# Sheet1.net
KiCad netlist of a schematic drawn in Altium Designer
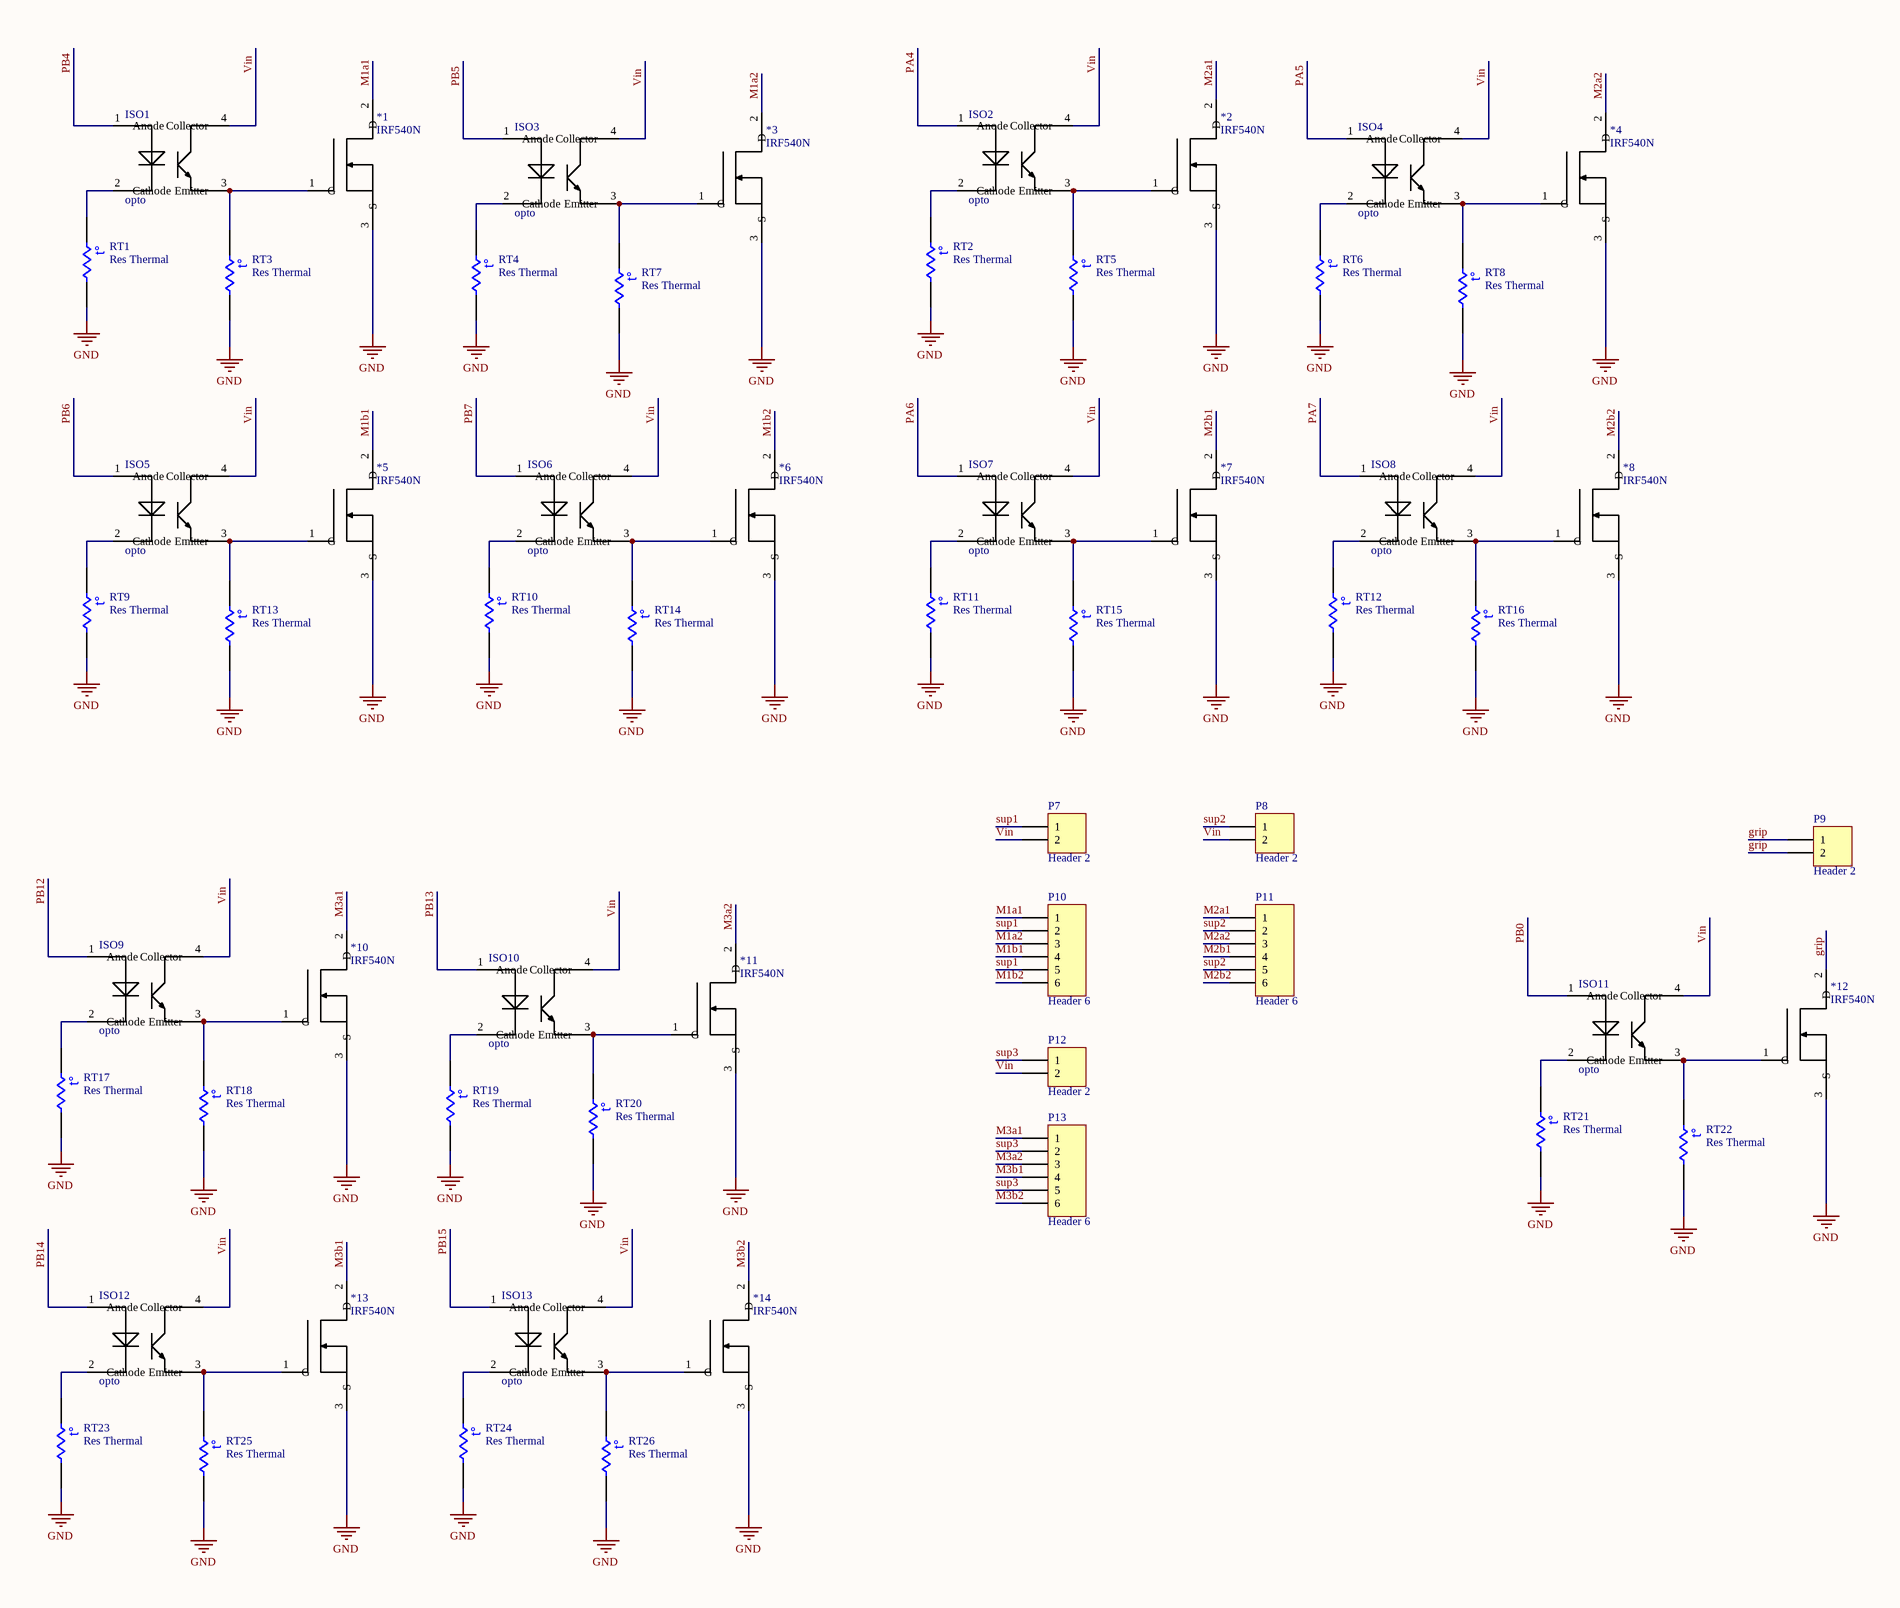
[diagram p0: Sheet1.SchDoc, left]
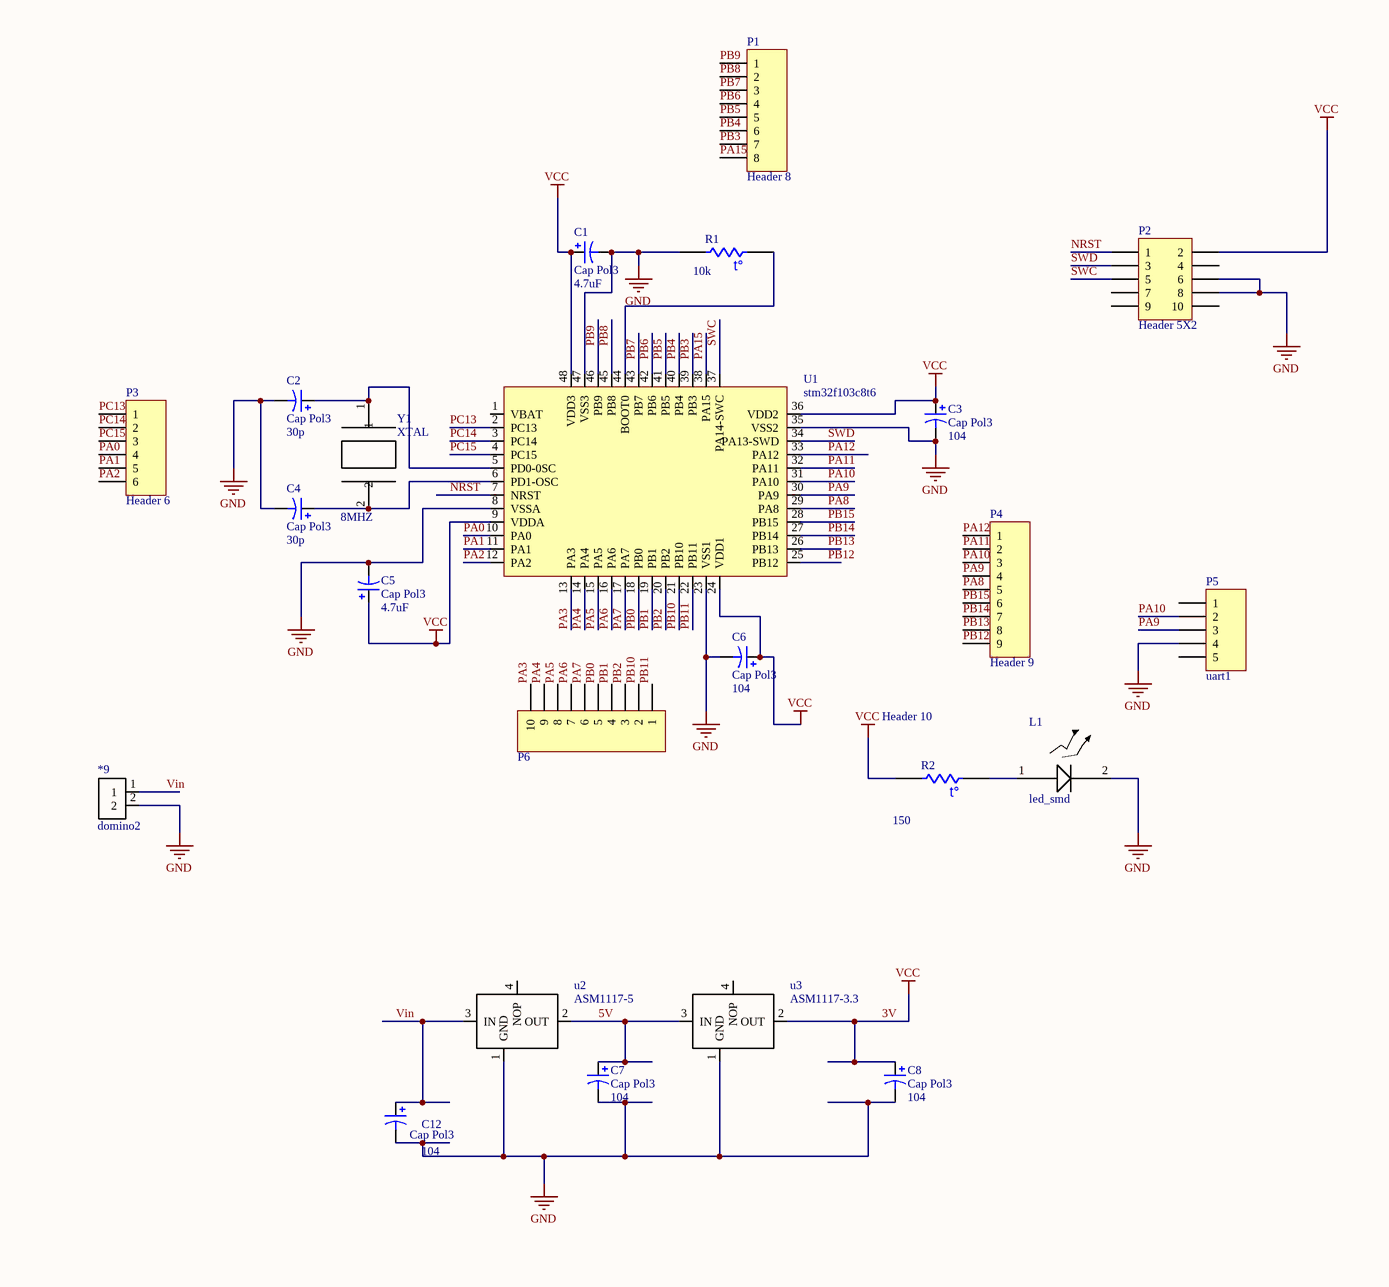
[diagram p1: Sheet1.SchDoc, right]

(export (version "E")
  (design (tool "Eeschema 10.0.6"))
  (components
    (comp (ref "*1")
      (value "IRF540N")
      (footprint "Pcbforslave:TO220")
      (libsource (lib "Schlib1") (part "IRF540N"))
    )
    (comp (ref "*2")
      (value "IRF540N")
      (footprint "Pcbforslave:TO220")
      (libsource (lib "Schlib1") (part "IRF540N"))
    )
    (comp (ref "*3")
      (value "IRF540N")
      (footprint "Pcbforslave:TO220")
      (libsource (lib "Schlib1") (part "IRF540N"))
    )
    (comp (ref "*4")
      (value "IRF540N")
      (footprint "Pcbforslave:TO220")
      (libsource (lib "Schlib1") (part "IRF540N"))
    )
    (comp (ref "*5")
      (value "IRF540N")
      (footprint "Pcbforslave:TO220")
      (libsource (lib "Schlib1") (part "IRF540N"))
    )
    (comp (ref "*6")
      (value "IRF540N")
      (footprint "Pcbforslave:TO220")
      (libsource (lib "Schlib1") (part "IRF540N"))
    )
    (comp (ref "*7")
      (value "IRF540N")
      (footprint "Pcbforslave:TO220")
      (libsource (lib "Schlib1") (part "IRF540N"))
    )
    (comp (ref "*8")
      (value "IRF540N")
      (footprint "Pcbforslave:TO220")
      (libsource (lib "Schlib1") (part "IRF540N"))
    )
    (comp (ref "*9")
      (value "domino2")
      (footprint "Pcbforslave:Domino_2")
      (libsource (lib "Schlib1") (part "domino2"))
    )
    (comp (ref "*10")
      (value "IRF540N")
      (footprint "Pcbforslave:TO220")
      (libsource (lib "Schlib1") (part "IRF540N"))
    )
    (comp (ref "*11")
      (value "IRF540N")
      (footprint "Pcbforslave:TO220")
      (libsource (lib "Schlib1") (part "IRF540N"))
    )
    (comp (ref "*12")
      (value "IRF540N")
      (footprint "Pcbforslave:TO220")
      (libsource (lib "Schlib1") (part "IRF540N"))
    )
    (comp (ref "*13")
      (value "IRF540N")
      (footprint "Pcbforslave:TO220")
      (libsource (lib "Schlib1") (part "IRF540N"))
    )
    (comp (ref "*14")
      (value "IRF540N")
      (footprint "Pcbforslave:TO220")
      (libsource (lib "Schlib1") (part "IRF540N"))
    )
    (comp (ref "C1")
      (value "Cap Pol3")
      (footprint "C0805")
      (description "Polarized Capacitor (Surface Mount)")
      (fields (field (name "ALTIUM_VALUE") "4.7uF") (field (name "PUBLISHER") "Altium Limited"))
      (libsource (lib "Miscellaneous Devices") (part "Cap Pol3"))
    )
    (comp (ref "C2")
      (value "Cap Pol3")
      (footprint "C0805")
      (description "Polarized Capacitor (Surface Mount)")
      (fields (field (name "ALTIUM_VALUE") "30p") (field (name "PUBLISHER") "Altium Limited"))
      (libsource (lib "Miscellaneous Devices") (part "Cap Pol3"))
    )
    (comp (ref "C3")
      (value "Cap Pol3")
      (footprint "C0805")
      (description "Polarized Capacitor (Surface Mount)")
      (fields (field (name "ALTIUM_VALUE") "104") (field (name "PUBLISHER") "Altium Limited"))
      (libsource (lib "Miscellaneous Devices") (part "Cap Pol3"))
    )
    (comp (ref "C4")
      (value "Cap Pol3")
      (footprint "C0805")
      (description "Polarized Capacitor (Surface Mount)")
      (fields (field (name "ALTIUM_VALUE") "30p") (field (name "PUBLISHER") "Altium Limited"))
      (libsource (lib "Miscellaneous Devices") (part "Cap Pol3"))
    )
    (comp (ref "C5")
      (value "Cap Pol3")
      (footprint "C0805")
      (description "Polarized Capacitor (Surface Mount)")
      (fields (field (name "ALTIUM_VALUE") "4.7uF") (field (name "PUBLISHER") "Altium Limited"))
      (libsource (lib "Miscellaneous Devices") (part "Cap Pol3"))
    )
    (comp (ref "C6")
      (value "Cap Pol3")
      (footprint "C0805")
      (description "Polarized Capacitor (Surface Mount)")
      (fields (field (name "ALTIUM_VALUE") "104") (field (name "PUBLISHER") "Altium Limited"))
      (libsource (lib "Miscellaneous Devices") (part "Cap Pol3"))
    )
    (comp (ref "C7")
      (value "Cap Pol3")
      (footprint "C0805")
      (description "Polarized Capacitor (Surface Mount)")
      (fields (field (name "ALTIUM_VALUE") "104") (field (name "PUBLISHER") "Altium Limited"))
      (libsource (lib "Miscellaneous Devices") (part "Cap Pol3"))
    )
    (comp (ref "C8")
      (value "Cap Pol3")
      (footprint "C0805")
      (description "Polarized Capacitor (Surface Mount)")
      (fields (field (name "ALTIUM_VALUE") "104") (field (name "PUBLISHER") "Altium Limited"))
      (libsource (lib "Miscellaneous Devices") (part "Cap Pol3"))
    )
    (comp (ref "C12")
      (value "Cap Pol3")
      (footprint "C0805")
      (description "Polarized Capacitor (Surface Mount)")
      (fields (field (name "ALTIUM_VALUE") "104") (field (name "PUBLISHER") "Altium Limited"))
      (libsource (lib "Miscellaneous Devices") (part "Cap Pol3"))
    )
    (comp (ref "ISO1")
      (value "opto")
      (footprint "Pcbforslave:opto_smd")
      (libsource (lib "Schlib1") (part "opto"))
    )
    (comp (ref "ISO2")
      (value "opto")
      (footprint "Pcbforslave:opto_smd")
      (libsource (lib "Schlib1") (part "opto"))
    )
    (comp (ref "ISO3")
      (value "opto")
      (footprint "Pcbforslave:opto_smd")
      (libsource (lib "Schlib1") (part "opto"))
    )
    (comp (ref "ISO4")
      (value "opto")
      (footprint "Pcbforslave:opto_smd")
      (libsource (lib "Schlib1") (part "opto"))
    )
    (comp (ref "ISO5")
      (value "opto")
      (footprint "Pcbforslave:opto_smd")
      (libsource (lib "Schlib1") (part "opto"))
    )
    (comp (ref "ISO6")
      (value "opto")
      (footprint "Pcbforslave:opto_smd")
      (libsource (lib "Schlib1") (part "opto"))
    )
    (comp (ref "ISO7")
      (value "opto")
      (footprint "Pcbforslave:opto_smd")
      (libsource (lib "Schlib1") (part "opto"))
    )
    (comp (ref "ISO8")
      (value "opto")
      (footprint "Pcbforslave:opto_smd")
      (libsource (lib "Schlib1") (part "opto"))
    )
    (comp (ref "ISO9")
      (value "opto")
      (footprint "Pcbforslave:opto_smd")
      (libsource (lib "Schlib1") (part "opto"))
    )
    (comp (ref "ISO10")
      (value "opto")
      (footprint "Pcbforslave:opto_smd")
      (libsource (lib "Schlib1") (part "opto"))
    )
    (comp (ref "ISO11")
      (value "opto")
      (footprint "Pcbforslave:opto_smd")
      (libsource (lib "Schlib1") (part "opto"))
    )
    (comp (ref "ISO12")
      (value "opto")
      (footprint "Pcbforslave:opto_smd")
      (libsource (lib "Schlib1") (part "opto"))
    )
    (comp (ref "ISO13")
      (value "opto")
      (footprint "Pcbforslave:opto_smd")
      (libsource (lib "Schlib1") (part "opto"))
    )
    (comp (ref "L1") (value "led_smd") (footprint "led_smd") (libsource (lib "Schlib1") (part "led_smd")))
    (comp (ref "P1")
      (value "Header 8")
      (footprint "HDR1X8")
      (description "Header, 8-Pin")
      (fields (field (name "PUBLISHER") "Altium Limited"))
      (libsource (lib "Miscellaneous Connectors") (part "Header 8"))
    )
    (comp (ref "P2")
      (value "Header 5X2")
      (footprint "HDR2X5")
      (description "Header, 5-Pin, Dual row")
      (fields (field (name "PUBLISHER") "Altium Limited"))
      (libsource (lib "Miscellaneous Connectors") (part "Header 5X2"))
    )
    (comp (ref "P3")
      (value "Header 6")
      (footprint "HDR1X6")
      (description "Header, 6-Pin")
      (fields (field (name "PUBLISHER") "Altium Limited"))
      (libsource (lib "Miscellaneous Connectors") (part "Header 6"))
    )
    (comp (ref "P4")
      (value "Header 9")
      (footprint "HDR1X9")
      (description "Header, 9-Pin")
      (fields (field (name "PUBLISHER") "Altium Limited"))
      (libsource (lib "Miscellaneous Connectors") (part "Header 9"))
    )
    (comp (ref "P5")
      (value "uart1")
      (footprint "HDR1X5")
      (description "Header, 5-Pin")
      (fields (field (name "PUBLISHER") "Altium Limited"))
      (libsource (lib "Miscellaneous Connectors") (part "Header 5"))
    )
    (comp (ref "P6")
      (value "Header 10")
      (footprint "HDR1X10")
      (description "Header, 10-Pin")
      (fields (field (name "PUBLISHER") "Altium Limited"))
      (libsource (lib "Miscellaneous Connectors") (part "Header 10"))
    )
    (comp (ref "P7")
      (value "Header 2")
      (footprint "HDR1X2")
      (description "Header, 2-Pin")
      (fields (field (name "PUBLISHER") "Altium Limited"))
      (libsource (lib "Miscellaneous Connectors") (part "Header 2"))
    )
    (comp (ref "P8")
      (value "Header 2")
      (footprint "HDR1X2")
      (description "Header, 2-Pin")
      (fields (field (name "PUBLISHER") "Altium Limited"))
      (libsource (lib "Miscellaneous Connectors") (part "Header 2"))
    )
    (comp (ref "P9")
      (value "Header 2")
      (footprint "HDR1X2")
      (description "Header, 2-Pin")
      (fields (field (name "PUBLISHER") "Altium Limited"))
      (libsource (lib "Miscellaneous Connectors") (part "Header 2"))
    )
    (comp (ref "P10")
      (value "Header 6")
      (footprint "HDR1X6")
      (description "Header, 6-Pin")
      (fields (field (name "PUBLISHER") "Altium Limited"))
      (libsource (lib "Miscellaneous Connectors") (part "Header 6"))
    )
    (comp (ref "P11")
      (value "Header 6")
      (footprint "HDR1X6")
      (description "Header, 6-Pin")
      (fields (field (name "PUBLISHER") "Altium Limited"))
      (libsource (lib "Miscellaneous Connectors") (part "Header 6"))
    )
    (comp (ref "P12")
      (value "Header 2")
      (footprint "HDR1X2")
      (description "Header, 2-Pin")
      (fields (field (name "PUBLISHER") "Altium Limited"))
      (libsource (lib "Miscellaneous Connectors") (part "Header 2"))
    )
    (comp (ref "P13")
      (value "Header 6")
      (footprint "HDR1X6")
      (description "Header, 6-Pin")
      (fields (field (name "PUBLISHER") "Altium Limited"))
      (libsource (lib "Miscellaneous Connectors") (part "Header 6"))
    )
    (comp (ref "R1")
      (value "10k")
      (footprint "6-0805_N")
      (description "Thermistor")
      (fields (field (name "PUBLISHER") "Altium Limited"))
      (libsource (lib "Miscellaneous Devices") (part "Res Thermal"))
    )
    (comp (ref "R2")
      (value "150")
      (footprint "6-0805_N")
      (description "Thermistor")
      (fields (field (name "PUBLISHER") "Altium Limited"))
      (libsource (lib "Miscellaneous Devices") (part "Res Thermal"))
    )
    (comp (ref "RT1")
      (value "Res Thermal")
      (footprint "6-0805_N")
      (description "Thermistor")
      (fields (field (name "PUBLISHER") "Altium Limited"))
      (libsource (lib "Miscellaneous Devices") (part "Res Thermal"))
    )
    (comp (ref "RT2")
      (value "Res Thermal")
      (footprint "6-0805_N")
      (description "Thermistor")
      (fields (field (name "PUBLISHER") "Altium Limited"))
      (libsource (lib "Miscellaneous Devices") (part "Res Thermal"))
    )
    (comp (ref "RT3")
      (value "Res Thermal")
      (footprint "6-0805_N")
      (description "Thermistor")
      (fields (field (name "PUBLISHER") "Altium Limited"))
      (libsource (lib "Miscellaneous Devices") (part "Res Thermal"))
    )
    (comp (ref "RT4")
      (value "Res Thermal")
      (footprint "6-0805_N")
      (description "Thermistor")
      (fields (field (name "PUBLISHER") "Altium Limited"))
      (libsource (lib "Miscellaneous Devices") (part "Res Thermal"))
    )
    (comp (ref "RT5")
      (value "Res Thermal")
      (footprint "6-0805_N")
      (description "Thermistor")
      (fields (field (name "PUBLISHER") "Altium Limited"))
      (libsource (lib "Miscellaneous Devices") (part "Res Thermal"))
    )
    (comp (ref "RT6")
      (value "Res Thermal")
      (footprint "6-0805_N")
      (description "Thermistor")
      (fields (field (name "PUBLISHER") "Altium Limited"))
      (libsource (lib "Miscellaneous Devices") (part "Res Thermal"))
    )
    (comp (ref "RT7")
      (value "Res Thermal")
      (footprint "6-0805_N")
      (description "Thermistor")
      (fields (field (name "PUBLISHER") "Altium Limited"))
      (libsource (lib "Miscellaneous Devices") (part "Res Thermal"))
    )
    (comp (ref "RT8")
      (value "Res Thermal")
      (footprint "6-0805_N")
      (description "Thermistor")
      (fields (field (name "PUBLISHER") "Altium Limited"))
      (libsource (lib "Miscellaneous Devices") (part "Res Thermal"))
    )
    (comp (ref "RT9")
      (value "Res Thermal")
      (footprint "6-0805_N")
      (description "Thermistor")
      (fields (field (name "PUBLISHER") "Altium Limited"))
      (libsource (lib "Miscellaneous Devices") (part "Res Thermal"))
    )
    (comp (ref "RT10")
      (value "Res Thermal")
      (footprint "6-0805_N")
      (description "Thermistor")
      (fields (field (name "PUBLISHER") "Altium Limited"))
      (libsource (lib "Miscellaneous Devices") (part "Res Thermal"))
    )
    (comp (ref "RT11")
      (value "Res Thermal")
      (footprint "6-0805_N")
      (description "Thermistor")
      (fields (field (name "PUBLISHER") "Altium Limited"))
      (libsource (lib "Miscellaneous Devices") (part "Res Thermal"))
    )
    (comp (ref "RT12")
      (value "Res Thermal")
      (footprint "6-0805_N")
      (description "Thermistor")
      (fields (field (name "PUBLISHER") "Altium Limited"))
      (libsource (lib "Miscellaneous Devices") (part "Res Thermal"))
    )
    (comp (ref "RT13")
      (value "Res Thermal")
      (footprint "6-0805_N")
      (description "Thermistor")
      (fields (field (name "PUBLISHER") "Altium Limited"))
      (libsource (lib "Miscellaneous Devices") (part "Res Thermal"))
    )
    (comp (ref "RT14")
      (value "Res Thermal")
      (footprint "6-0805_N")
      (description "Thermistor")
      (fields (field (name "PUBLISHER") "Altium Limited"))
      (libsource (lib "Miscellaneous Devices") (part "Res Thermal"))
    )
    (comp (ref "RT15")
      (value "Res Thermal")
      (footprint "6-0805_N")
      (description "Thermistor")
      (fields (field (name "PUBLISHER") "Altium Limited"))
      (libsource (lib "Miscellaneous Devices") (part "Res Thermal"))
    )
    (comp (ref "RT16")
      (value "Res Thermal")
      (footprint "6-0805_N")
      (description "Thermistor")
      (fields (field (name "PUBLISHER") "Altium Limited"))
      (libsource (lib "Miscellaneous Devices") (part "Res Thermal"))
    )
    (comp (ref "RT17")
      (value "Res Thermal")
      (footprint "6-0805_N")
      (description "Thermistor")
      (fields (field (name "PUBLISHER") "Altium Limited"))
      (libsource (lib "Miscellaneous Devices") (part "Res Thermal"))
    )
    (comp (ref "RT18")
      (value "Res Thermal")
      (footprint "6-0805_N")
      (description "Thermistor")
      (fields (field (name "PUBLISHER") "Altium Limited"))
      (libsource (lib "Miscellaneous Devices") (part "Res Thermal"))
    )
    (comp (ref "RT19")
      (value "Res Thermal")
      (footprint "6-0805_N")
      (description "Thermistor")
      (fields (field (name "PUBLISHER") "Altium Limited"))
      (libsource (lib "Miscellaneous Devices") (part "Res Thermal"))
    )
    (comp (ref "RT20")
      (value "Res Thermal")
      (footprint "6-0805_N")
      (description "Thermistor")
      (fields (field (name "PUBLISHER") "Altium Limited"))
      (libsource (lib "Miscellaneous Devices") (part "Res Thermal"))
    )
    (comp (ref "RT21")
      (value "Res Thermal")
      (footprint "6-0805_N")
      (description "Thermistor")
      (fields (field (name "PUBLISHER") "Altium Limited"))
      (libsource (lib "Miscellaneous Devices") (part "Res Thermal"))
    )
    (comp (ref "RT22")
      (value "Res Thermal")
      (footprint "6-0805_N")
      (description "Thermistor")
      (fields (field (name "PUBLISHER") "Altium Limited"))
      (libsource (lib "Miscellaneous Devices") (part "Res Thermal"))
    )
    (comp (ref "RT23")
      (value "Res Thermal")
      (footprint "6-0805_N")
      (description "Thermistor")
      (fields (field (name "PUBLISHER") "Altium Limited"))
      (libsource (lib "Miscellaneous Devices") (part "Res Thermal"))
    )
    (comp (ref "RT24")
      (value "Res Thermal")
      (footprint "6-0805_N")
      (description "Thermistor")
      (fields (field (name "PUBLISHER") "Altium Limited"))
      (libsource (lib "Miscellaneous Devices") (part "Res Thermal"))
    )
    (comp (ref "RT25")
      (value "Res Thermal")
      (footprint "6-0805_N")
      (description "Thermistor")
      (fields (field (name "PUBLISHER") "Altium Limited"))
      (libsource (lib "Miscellaneous Devices") (part "Res Thermal"))
    )
    (comp (ref "RT26")
      (value "Res Thermal")
      (footprint "6-0805_N")
      (description "Thermistor")
      (fields (field (name "PUBLISHER") "Altium Limited"))
      (libsource (lib "Miscellaneous Devices") (part "Res Thermal"))
    )
    (comp (ref "U1")
      (value "stm32f103c8t6")
      (footprint "Pcbforslave:LQFP48_stm32")
      (libsource (lib "Schlib1") (part "stm32f103c8t6"))
    )
    (comp (ref "u2") (value "ASM1117-5") (footprint "SOT223") (libsource (lib "Schlib1") (part "ASM1117-5")))
    (comp (ref "u3")
      (value "ASM1117-3.3")
      (footprint "SOT223")
      (libsource (lib "Schlib1") (part "ASM1117-5"))
    )
    (comp (ref "Y1")
      (value "XTAL")
      (footprint "xtal_smd")
      (fields (field (name "ALTIUM_VALUE") "8MHZ"))
      (libsource (lib "Schlib1") (part "XTAL"))
    )
  )
  (nets
    (net (code "1") (name "/5V") (class "Default")
      (node (ref "C7") (pin "1") (pinfunction "1_1") (pintype "passive"))
      (node (ref "u2") (pin "2") (pinfunction "OUT_2") (pintype "passive"))
      (node (ref "u3") (pin "3") (pinfunction "IN_3") (pintype "passive"))
    )
    (net (code "2") (name "/M1a1") (class "Default")
      (node (ref "*1") (pin "2") (pinfunction "D_2") (pintype "passive"))
      (node (ref "P10") (pin "1") (pinfunction "1_1") (pintype "passive"))
    )
    (net (code "3") (name "/M1a2") (class "Default")
      (node (ref "*3") (pin "2") (pinfunction "D_2") (pintype "passive"))
      (node (ref "P10") (pin "3") (pinfunction "3_3") (pintype "passive"))
    )
    (net (code "4") (name "/M1b1") (class "Default")
      (node (ref "*5") (pin "2") (pinfunction "D_2") (pintype "passive"))
      (node (ref "P10") (pin "4") (pinfunction "4_4") (pintype "passive"))
    )
    (net (code "5") (name "/M1b2") (class "Default")
      (node (ref "*6") (pin "2") (pinfunction "D_2") (pintype "passive"))
      (node (ref "P10") (pin "6") (pinfunction "6_6") (pintype "passive"))
    )
    (net (code "6") (name "/M2a1") (class "Default")
      (node (ref "*2") (pin "2") (pinfunction "D_2") (pintype "passive"))
      (node (ref "P11") (pin "1") (pinfunction "1_1") (pintype "passive"))
    )
    (net (code "7") (name "/M2a2") (class "Default")
      (node (ref "*4") (pin "2") (pinfunction "D_2") (pintype "passive"))
      (node (ref "P11") (pin "3") (pinfunction "3_3") (pintype "passive"))
    )
    (net (code "8") (name "/M2b1") (class "Default")
      (node (ref "*7") (pin "2") (pinfunction "D_2") (pintype "passive"))
      (node (ref "P11") (pin "4") (pinfunction "4_4") (pintype "passive"))
    )
    (net (code "9") (name "/M2b2") (class "Default")
      (node (ref "*8") (pin "2") (pinfunction "D_2") (pintype "passive"))
      (node (ref "P11") (pin "6") (pinfunction "6_6") (pintype "passive"))
    )
    (net (code "10") (name "/M3a1") (class "Default")
      (node (ref "*10") (pin "2") (pinfunction "D_2") (pintype "passive"))
      (node (ref "P13") (pin "1") (pinfunction "1_1") (pintype "passive"))
    )
    (net (code "11") (name "/M3a2") (class "Default")
      (node (ref "*11") (pin "2") (pinfunction "D_2") (pintype "passive"))
      (node (ref "P13") (pin "3") (pinfunction "3_3") (pintype "passive"))
    )
    (net (code "12") (name "/M3b1") (class "Default")
      (node (ref "*13") (pin "2") (pinfunction "D_2") (pintype "passive"))
      (node (ref "P13") (pin "4") (pinfunction "4_4") (pintype "passive"))
    )
    (net (code "13") (name "/M3b2") (class "Default")
      (node (ref "*14") (pin "2") (pinfunction "D_2") (pintype "passive"))
      (node (ref "P13") (pin "6") (pinfunction "6_6") (pintype "passive"))
    )
    (net (code "14") (name "/NRST") (class "Default")
      (node (ref "P2") (pin "1") (pinfunction "1_1") (pintype "passive"))
      (node (ref "U1") (pin "7") (pinfunction "NRST_7") (pintype "passive"))
    )
    (net (code "15") (name "/PA0") (class "Default")
      (node (ref "P3") (pin "4") (pinfunction "4_4") (pintype "passive"))
      (node (ref "U1") (pin "10") (pinfunction "PA0_10") (pintype "passive"))
    )
    (net (code "16") (name "/PA1") (class "Default")
      (node (ref "P3") (pin "5") (pinfunction "5_5") (pintype "passive"))
      (node (ref "U1") (pin "11") (pinfunction "PA1_11") (pintype "passive"))
    )
    (net (code "17") (name "/PA2") (class "Default")
      (node (ref "P3") (pin "6") (pinfunction "6_6") (pintype "passive"))
      (node (ref "U1") (pin "12") (pinfunction "PA2_12") (pintype "passive"))
    )
    (net (code "18") (name "/PA3") (class "Default")
      (node (ref "P6") (pin "10") (pinfunction "10_10") (pintype "passive"))
      (node (ref "U1") (pin "13") (pinfunction "PA3_13") (pintype "passive"))
    )
    (net (code "19") (name "/PA4") (class "Default")
      (node (ref "ISO2") (pin "1") (pinfunction "Anode_1") (pintype "passive"))
      (node (ref "P6") (pin "9") (pinfunction "9_9") (pintype "passive"))
      (node (ref "U1") (pin "14") (pinfunction "PA4_14") (pintype "passive"))
    )
    (net (code "20") (name "/PA5") (class "Default")
      (node (ref "ISO4") (pin "1") (pinfunction "Anode_1") (pintype "passive"))
      (node (ref "P6") (pin "8") (pinfunction "8_8") (pintype "passive"))
      (node (ref "U1") (pin "15") (pinfunction "PA5_15") (pintype "passive"))
    )
    (net (code "21") (name "/PA6") (class "Default")
      (node (ref "ISO7") (pin "1") (pinfunction "Anode_1") (pintype "passive"))
      (node (ref "P6") (pin "7") (pinfunction "7_7") (pintype "passive"))
      (node (ref "U1") (pin "16") (pinfunction "PA6_16") (pintype "passive"))
    )
    (net (code "22") (name "/PA7") (class "Default")
      (node (ref "ISO8") (pin "1") (pinfunction "Anode_1") (pintype "passive"))
      (node (ref "P6") (pin "6") (pinfunction "6_6") (pintype "passive"))
      (node (ref "U1") (pin "17") (pinfunction "PA7_17") (pintype "passive"))
    )
    (net (code "23") (name "/PA8") (class "Default")
      (node (ref "P4") (pin "5") (pinfunction "5_5") (pintype "passive"))
      (node (ref "U1") (pin "29") (pinfunction "PA8_29") (pintype "passive"))
    )
    (net (code "24") (name "/PA9") (class "Default")
      (node (ref "P4") (pin "4") (pinfunction "4_4") (pintype "passive"))
      (node (ref "P5") (pin "3") (pinfunction "3_3") (pintype "passive"))
      (node (ref "U1") (pin "30") (pinfunction "PA9_30") (pintype "passive"))
    )
    (net (code "25") (name "/PA10") (class "Default")
      (node (ref "P4") (pin "3") (pinfunction "3_3") (pintype "passive"))
      (node (ref "P5") (pin "2") (pinfunction "2_2") (pintype "passive"))
      (node (ref "U1") (pin "31") (pinfunction "PA10_31") (pintype "passive"))
    )
    (net (code "26") (name "/PA11") (class "Default")
      (node (ref "P4") (pin "2") (pinfunction "2_2") (pintype "passive"))
      (node (ref "U1") (pin "32") (pinfunction "PA11_32") (pintype "passive"))
    )
    (net (code "27") (name "/PA12") (class "Default")
      (node (ref "P4") (pin "1") (pinfunction "1_1") (pintype "passive"))
      (node (ref "U1") (pin "33") (pinfunction "PA12_33") (pintype "passive"))
    )
    (net (code "28") (name "/PA15") (class "Default")
      (node (ref "P1") (pin "8") (pinfunction "8_8") (pintype "passive"))
      (node (ref "U1") (pin "38") (pinfunction "PA15_38") (pintype "passive"))
    )
    (net (code "29") (name "/PB0") (class "Default")
      (node (ref "ISO11") (pin "1") (pinfunction "Anode_1") (pintype "passive"))
      (node (ref "P6") (pin "5") (pinfunction "5_5") (pintype "passive"))
      (node (ref "U1") (pin "18") (pinfunction "PB0_18") (pintype "passive"))
    )
    (net (code "30") (name "/PB1") (class "Default")
      (node (ref "P6") (pin "4") (pinfunction "4_4") (pintype "passive"))
      (node (ref "U1") (pin "19") (pinfunction "PB1_19") (pintype "passive"))
    )
    (net (code "31") (name "/PB2") (class "Default")
      (node (ref "P6") (pin "3") (pinfunction "3_3") (pintype "passive"))
      (node (ref "U1") (pin "20") (pinfunction "PB2_20") (pintype "passive"))
    )
    (net (code "32") (name "/PB3") (class "Default")
      (node (ref "P1") (pin "7") (pinfunction "7_7") (pintype "passive"))
      (node (ref "U1") (pin "39") (pinfunction "PB3_39") (pintype "passive"))
    )
    (net (code "33") (name "/PB4") (class "Default")
      (node (ref "ISO1") (pin "1") (pinfunction "Anode_1") (pintype "passive"))
      (node (ref "P1") (pin "6") (pinfunction "6_6") (pintype "passive"))
      (node (ref "U1") (pin "40") (pinfunction "PB4_40") (pintype "passive"))
    )
    (net (code "34") (name "/PB5") (class "Default")
      (node (ref "ISO3") (pin "1") (pinfunction "Anode_1") (pintype "passive"))
      (node (ref "P1") (pin "5") (pinfunction "5_5") (pintype "passive"))
      (node (ref "U1") (pin "41") (pinfunction "PB5_41") (pintype "passive"))
    )
    (net (code "35") (name "/PB6") (class "Default")
      (node (ref "ISO5") (pin "1") (pinfunction "Anode_1") (pintype "passive"))
      (node (ref "P1") (pin "4") (pinfunction "4_4") (pintype "passive"))
      (node (ref "U1") (pin "42") (pinfunction "PB6_42") (pintype "passive"))
    )
    (net (code "36") (name "/PB7") (class "Default")
      (node (ref "ISO6") (pin "1") (pinfunction "Anode_1") (pintype "passive"))
      (node (ref "P1") (pin "3") (pinfunction "3_3") (pintype "passive"))
      (node (ref "U1") (pin "43") (pinfunction "PB7_43") (pintype "passive"))
    )
    (net (code "37") (name "/PB8") (class "Default")
      (node (ref "P1") (pin "2") (pinfunction "2_2") (pintype "passive"))
      (node (ref "U1") (pin "45") (pinfunction "PB8_45") (pintype "passive"))
    )
    (net (code "38") (name "/PB9") (class "Default")
      (node (ref "P1") (pin "1") (pinfunction "1_1") (pintype "passive"))
      (node (ref "U1") (pin "46") (pinfunction "PB9_46") (pintype "passive"))
    )
    (net (code "39") (name "/PB10") (class "Default")
      (node (ref "P6") (pin "2") (pinfunction "2_2") (pintype "passive"))
      (node (ref "U1") (pin "21") (pinfunction "PB10_21") (pintype "passive"))
    )
    (net (code "40") (name "/PB11") (class "Default")
      (node (ref "P6") (pin "1") (pinfunction "1_1") (pintype "passive"))
      (node (ref "U1") (pin "22") (pinfunction "PB11_22") (pintype "passive"))
    )
    (net (code "41") (name "/PB12") (class "Default")
      (node (ref "ISO9") (pin "1") (pinfunction "Anode_1") (pintype "passive"))
      (node (ref "P4") (pin "9") (pinfunction "9_9") (pintype "passive"))
      (node (ref "U1") (pin "25") (pinfunction "PB12_25") (pintype "passive"))
    )
    (net (code "42") (name "/PB13") (class "Default")
      (node (ref "ISO10") (pin "1") (pinfunction "Anode_1") (pintype "passive"))
      (node (ref "P4") (pin "8") (pinfunction "8_8") (pintype "passive"))
      (node (ref "U1") (pin "26") (pinfunction "PB13_26") (pintype "passive"))
    )
    (net (code "43") (name "/PB14") (class "Default")
      (node (ref "ISO12") (pin "1") (pinfunction "Anode_1") (pintype "passive"))
      (node (ref "P4") (pin "7") (pinfunction "7_7") (pintype "passive"))
      (node (ref "U1") (pin "27") (pinfunction "PB14_27") (pintype "passive"))
    )
    (net (code "44") (name "/PB15") (class "Default")
      (node (ref "ISO13") (pin "1") (pinfunction "Anode_1") (pintype "passive"))
      (node (ref "P4") (pin "6") (pinfunction "6_6") (pintype "passive"))
      (node (ref "U1") (pin "28") (pinfunction "PB15_28") (pintype "passive"))
    )
    (net (code "45") (name "/PC13") (class "Default")
      (node (ref "P3") (pin "1") (pinfunction "1_1") (pintype "passive"))
      (node (ref "U1") (pin "2") (pinfunction "PC13_2") (pintype "passive"))
    )
    (net (code "46") (name "/PC14") (class "Default")
      (node (ref "P3") (pin "2") (pinfunction "2_2") (pintype "passive"))
      (node (ref "U1") (pin "3") (pinfunction "PC14_3") (pintype "passive"))
    )
    (net (code "47") (name "/PC15") (class "Default")
      (node (ref "P3") (pin "3") (pinfunction "3_3") (pintype "passive"))
      (node (ref "U1") (pin "4") (pinfunction "PC15_4") (pintype "passive"))
    )
    (net (code "48") (name "/SWC") (class "Default")
      (node (ref "P2") (pin "5") (pinfunction "5_5") (pintype "passive"))
      (node (ref "U1") (pin "37") (pinfunction "PA14-SWC_37") (pintype "passive"))
    )
    (net (code "49") (name "/SWD") (class "Default")
      (node (ref "P2") (pin "3") (pinfunction "3_3") (pintype "passive"))
      (node (ref "U1") (pin "34") (pinfunction "PA13-SWD_34") (pintype "passive"))
    )
    (net (code "50") (name "/Vin") (class "Default")
      (node (ref "*9") (pin "1") (pinfunction "1_1") (pintype "passive"))
      (node (ref "C12") (pin "1") (pinfunction "1_1") (pintype "passive"))
      (node (ref "ISO1") (pin "4") (pinfunction "Collector_4") (pintype "passive"))
      (node (ref "ISO10") (pin "4") (pinfunction "Collector_4") (pintype "passive"))
      (node (ref "ISO11") (pin "4") (pinfunction "Collector_4") (pintype "passive"))
      (node (ref "ISO12") (pin "4") (pinfunction "Collector_4") (pintype "passive"))
      (node (ref "ISO13") (pin "4") (pinfunction "Collector_4") (pintype "passive"))
      (node (ref "ISO2") (pin "4") (pinfunction "Collector_4") (pintype "passive"))
      (node (ref "ISO3") (pin "4") (pinfunction "Collector_4") (pintype "passive"))
      (node (ref "ISO4") (pin "4") (pinfunction "Collector_4") (pintype "passive"))
      (node (ref "ISO5") (pin "4") (pinfunction "Collector_4") (pintype "passive"))
      (node (ref "ISO6") (pin "4") (pinfunction "Collector_4") (pintype "passive"))
      (node (ref "ISO7") (pin "4") (pinfunction "Collector_4") (pintype "passive"))
      (node (ref "ISO8") (pin "4") (pinfunction "Collector_4") (pintype "passive"))
      (node (ref "ISO9") (pin "4") (pinfunction "Collector_4") (pintype "passive"))
      (node (ref "P12") (pin "2") (pinfunction "2_2") (pintype "passive"))
      (node (ref "P7") (pin "2") (pinfunction "2_2") (pintype "passive"))
      (node (ref "P8") (pin "2") (pinfunction "2_2") (pintype "passive"))
      (node (ref "u2") (pin "3") (pinfunction "IN_3") (pintype "passive"))
    )
    (net (code "51") (name "/grip") (class "Default")
      (node (ref "*12") (pin "2") (pinfunction "D_2") (pintype "passive"))
      (node (ref "P9") (pin "1") (pinfunction "1_1") (pintype "passive"))
      (node (ref "P9") (pin "2") (pinfunction "2_2") (pintype "passive"))
    )
    (net (code "52") (name "/sup1") (class "Default")
      (node (ref "P10") (pin "2") (pinfunction "2_2") (pintype "passive"))
      (node (ref "P10") (pin "5") (pinfunction "5_5") (pintype "passive"))
      (node (ref "P7") (pin "1") (pinfunction "1_1") (pintype "passive"))
    )
    (net (code "53") (name "/sup2") (class "Default")
      (node (ref "P11") (pin "2") (pinfunction "2_2") (pintype "passive"))
      (node (ref "P11") (pin "5") (pinfunction "5_5") (pintype "passive"))
      (node (ref "P8") (pin "1") (pinfunction "1_1") (pintype "passive"))
    )
    (net (code "54") (name "/sup3") (class "Default")
      (node (ref "P12") (pin "1") (pinfunction "1_1") (pintype "passive"))
      (node (ref "P13") (pin "2") (pinfunction "2_2") (pintype "passive"))
      (node (ref "P13") (pin "5") (pinfunction "5_5") (pintype "passive"))
    )
    (net (code "55") (name "GND") (class "Default")
      (node (ref "*1") (pin "3") (pinfunction "S_3") (pintype "passive"))
      (node (ref "*10") (pin "3") (pinfunction "S_3") (pintype "passive"))
      (node (ref "*11") (pin "3") (pinfunction "S_3") (pintype "passive"))
      (node (ref "*12") (pin "3") (pinfunction "S_3") (pintype "passive"))
      (node (ref "*13") (pin "3") (pinfunction "S_3") (pintype "passive"))
      (node (ref "*14") (pin "3") (pinfunction "S_3") (pintype "passive"))
      (node (ref "*2") (pin "3") (pinfunction "S_3") (pintype "passive"))
      (node (ref "*3") (pin "3") (pinfunction "S_3") (pintype "passive"))
      (node (ref "*4") (pin "3") (pinfunction "S_3") (pintype "passive"))
      (node (ref "*5") (pin "3") (pinfunction "S_3") (pintype "passive"))
      (node (ref "*6") (pin "3") (pinfunction "S_3") (pintype "passive"))
      (node (ref "*7") (pin "3") (pinfunction "S_3") (pintype "passive"))
      (node (ref "*8") (pin "3") (pinfunction "S_3") (pintype "passive"))
      (node (ref "*9") (pin "2") (pinfunction "2_2") (pintype "passive"))
      (node (ref "C1") (pin "2") (pinfunction "2_2") (pintype "passive"))
      (node (ref "C12") (pin "2") (pinfunction "2_2") (pintype "passive"))
      (node (ref "C2") (pin "2") (pinfunction "2_2") (pintype "passive"))
      (node (ref "C3") (pin "2") (pinfunction "2_2") (pintype "passive"))
      (node (ref "C4") (pin "2") (pinfunction "2_2") (pintype "passive"))
      (node (ref "C5") (pin "2") (pinfunction "2_2") (pintype "passive"))
      (node (ref "C6") (pin "2") (pinfunction "2_2") (pintype "passive"))
      (node (ref "C7") (pin "2") (pinfunction "2_2") (pintype "passive"))
      (node (ref "C8") (pin "2") (pinfunction "2_2") (pintype "passive"))
      (node (ref "L1") (pin "2") (pintype "passive"))
      (node (ref "P2") (pin "6") (pinfunction "6_6") (pintype "passive"))
      (node (ref "P2") (pin "8") (pinfunction "8_8") (pintype "passive"))
      (node (ref "P5") (pin "4") (pinfunction "4_4") (pintype "passive"))
      (node (ref "R1") (pin "2") (pinfunction "2_2") (pintype "passive"))
      (node (ref "RT1") (pin "2") (pinfunction "2_2") (pintype "passive"))
      (node (ref "RT10") (pin "2") (pinfunction "2_2") (pintype "passive"))
      (node (ref "RT11") (pin "2") (pinfunction "2_2") (pintype "passive"))
      (node (ref "RT12") (pin "2") (pinfunction "2_2") (pintype "passive"))
      (node (ref "RT13") (pin "2") (pinfunction "2_2") (pintype "passive"))
      (node (ref "RT14") (pin "2") (pinfunction "2_2") (pintype "passive"))
      (node (ref "RT15") (pin "2") (pinfunction "2_2") (pintype "passive"))
      (node (ref "RT16") (pin "2") (pinfunction "2_2") (pintype "passive"))
      (node (ref "RT17") (pin "2") (pinfunction "2_2") (pintype "passive"))
      (node (ref "RT18") (pin "2") (pinfunction "2_2") (pintype "passive"))
      (node (ref "RT19") (pin "2") (pinfunction "2_2") (pintype "passive"))
      (node (ref "RT2") (pin "2") (pinfunction "2_2") (pintype "passive"))
      (node (ref "RT20") (pin "2") (pinfunction "2_2") (pintype "passive"))
      (node (ref "RT21") (pin "2") (pinfunction "2_2") (pintype "passive"))
      (node (ref "RT22") (pin "2") (pinfunction "2_2") (pintype "passive"))
      (node (ref "RT23") (pin "2") (pinfunction "2_2") (pintype "passive"))
      (node (ref "RT24") (pin "2") (pinfunction "2_2") (pintype "passive"))
      (node (ref "RT25") (pin "2") (pinfunction "2_2") (pintype "passive"))
      (node (ref "RT26") (pin "2") (pinfunction "2_2") (pintype "passive"))
      (node (ref "RT3") (pin "2") (pinfunction "2_2") (pintype "passive"))
      (node (ref "RT4") (pin "2") (pinfunction "2_2") (pintype "passive"))
      (node (ref "RT5") (pin "2") (pinfunction "2_2") (pintype "passive"))
      (node (ref "RT6") (pin "2") (pinfunction "2_2") (pintype "passive"))
      (node (ref "RT7") (pin "2") (pinfunction "2_2") (pintype "passive"))
      (node (ref "RT8") (pin "2") (pinfunction "2_2") (pintype "passive"))
      (node (ref "RT9") (pin "2") (pinfunction "2_2") (pintype "passive"))
      (node (ref "U1") (pin "23") (pinfunction "VSS1_23") (pintype "passive"))
      (node (ref "U1") (pin "35") (pinfunction "VSS2_35") (pintype "passive"))
      (node (ref "U1") (pin "47") (pinfunction "VSS3_47") (pintype "passive"))
      (node (ref "U1") (pin "8") (pinfunction "VSSA_8") (pintype "passive"))
      (node (ref "u2") (pin "1") (pinfunction "GND_1") (pintype "passive"))
      (node (ref "u3") (pin "1") (pinfunction "GND_1") (pintype "passive"))
    )
    (net (code "56") (name "Net-(*1-G)") (class "Default")
      (node (ref "*1") (pin "1") (pinfunction "G_1") (pintype "passive"))
      (node (ref "ISO1") (pin "3") (pinfunction "Emitter_3") (pintype "passive"))
      (node (ref "RT3") (pin "1") (pinfunction "1_1") (pintype "passive"))
    )
    (net (code "57") (name "Net-(*2-G)") (class "Default")
      (node (ref "*2") (pin "1") (pinfunction "G_1") (pintype "passive"))
      (node (ref "ISO2") (pin "3") (pinfunction "Emitter_3") (pintype "passive"))
      (node (ref "RT5") (pin "1") (pinfunction "1_1") (pintype "passive"))
    )
    (net (code "58") (name "Net-(*3-G)") (class "Default")
      (node (ref "*3") (pin "1") (pinfunction "G_1") (pintype "passive"))
      (node (ref "ISO3") (pin "3") (pinfunction "Emitter_3") (pintype "passive"))
      (node (ref "RT7") (pin "1") (pinfunction "1_1") (pintype "passive"))
    )
    (net (code "59") (name "Net-(*4-G)") (class "Default")
      (node (ref "*4") (pin "1") (pinfunction "G_1") (pintype "passive"))
      (node (ref "ISO4") (pin "3") (pinfunction "Emitter_3") (pintype "passive"))
      (node (ref "RT8") (pin "1") (pinfunction "1_1") (pintype "passive"))
    )
    (net (code "60") (name "Net-(*5-G)") (class "Default")
      (node (ref "*5") (pin "1") (pinfunction "G_1") (pintype "passive"))
      (node (ref "ISO5") (pin "3") (pinfunction "Emitter_3") (pintype "passive"))
      (node (ref "RT13") (pin "1") (pinfunction "1_1") (pintype "passive"))
    )
    (net (code "61") (name "Net-(*6-G)") (class "Default")
      (node (ref "*6") (pin "1") (pinfunction "G_1") (pintype "passive"))
      (node (ref "ISO6") (pin "3") (pinfunction "Emitter_3") (pintype "passive"))
      (node (ref "RT14") (pin "1") (pinfunction "1_1") (pintype "passive"))
    )
    (net (code "62") (name "Net-(*7-G)") (class "Default")
      (node (ref "*7") (pin "1") (pinfunction "G_1") (pintype "passive"))
      (node (ref "ISO7") (pin "3") (pinfunction "Emitter_3") (pintype "passive"))
      (node (ref "RT15") (pin "1") (pinfunction "1_1") (pintype "passive"))
    )
    (net (code "63") (name "Net-(*8-G)") (class "Default")
      (node (ref "*8") (pin "1") (pinfunction "G_1") (pintype "passive"))
      (node (ref "ISO8") (pin "3") (pinfunction "Emitter_3") (pintype "passive"))
      (node (ref "RT16") (pin "1") (pinfunction "1_1") (pintype "passive"))
    )
    (net (code "64") (name "Net-(*10-G)") (class "Default")
      (node (ref "*10") (pin "1") (pinfunction "G_1") (pintype "passive"))
      (node (ref "ISO9") (pin "3") (pinfunction "Emitter_3") (pintype "passive"))
      (node (ref "RT18") (pin "1") (pinfunction "1_1") (pintype "passive"))
    )
    (net (code "65") (name "Net-(*11-G)") (class "Default")
      (node (ref "*11") (pin "1") (pinfunction "G_1") (pintype "passive"))
      (node (ref "ISO10") (pin "3") (pinfunction "Emitter_3") (pintype "passive"))
      (node (ref "RT20") (pin "1") (pinfunction "1_1") (pintype "passive"))
    )
    (net (code "66") (name "Net-(*12-G)") (class "Default")
      (node (ref "*12") (pin "1") (pinfunction "G_1") (pintype "passive"))
      (node (ref "ISO11") (pin "3") (pinfunction "Emitter_3") (pintype "passive"))
      (node (ref "RT22") (pin "1") (pinfunction "1_1") (pintype "passive"))
    )
    (net (code "67") (name "Net-(*13-G)") (class "Default")
      (node (ref "*13") (pin "1") (pinfunction "G_1") (pintype "passive"))
      (node (ref "ISO12") (pin "3") (pinfunction "Emitter_3") (pintype "passive"))
      (node (ref "RT25") (pin "1") (pinfunction "1_1") (pintype "passive"))
    )
    (net (code "68") (name "Net-(*14-G)") (class "Default")
      (node (ref "*14") (pin "1") (pinfunction "G_1") (pintype "passive"))
      (node (ref "ISO13") (pin "3") (pinfunction "Emitter_3") (pintype "passive"))
      (node (ref "RT26") (pin "1") (pinfunction "1_1") (pintype "passive"))
    )
    (net (code "69") (name "Net-(ISO1-Cathode)") (class "Default")
      (node (ref "ISO1") (pin "2") (pinfunction "Cathode_2") (pintype "passive"))
      (node (ref "RT1") (pin "1") (pinfunction "1_1") (pintype "passive"))
    )
    (net (code "70") (name "Net-(ISO2-Cathode)") (class "Default")
      (node (ref "ISO2") (pin "2") (pinfunction "Cathode_2") (pintype "passive"))
      (node (ref "RT2") (pin "1") (pinfunction "1_1") (pintype "passive"))
    )
    (net (code "71") (name "Net-(ISO3-Cathode)") (class "Default")
      (node (ref "ISO3") (pin "2") (pinfunction "Cathode_2") (pintype "passive"))
      (node (ref "RT4") (pin "1") (pinfunction "1_1") (pintype "passive"))
    )
    (net (code "72") (name "Net-(ISO4-Cathode)") (class "Default")
      (node (ref "ISO4") (pin "2") (pinfunction "Cathode_2") (pintype "passive"))
      (node (ref "RT6") (pin "1") (pinfunction "1_1") (pintype "passive"))
    )
    (net (code "73") (name "Net-(ISO5-Cathode)") (class "Default")
      (node (ref "ISO5") (pin "2") (pinfunction "Cathode_2") (pintype "passive"))
      (node (ref "RT9") (pin "1") (pinfunction "1_1") (pintype "passive"))
    )
    (net (code "74") (name "Net-(ISO6-Cathode)") (class "Default")
      (node (ref "ISO6") (pin "2") (pinfunction "Cathode_2") (pintype "passive"))
      (node (ref "RT10") (pin "1") (pinfunction "1_1") (pintype "passive"))
    )
    (net (code "75") (name "Net-(ISO7-Cathode)") (class "Default")
      (node (ref "ISO7") (pin "2") (pinfunction "Cathode_2") (pintype "passive"))
      (node (ref "RT11") (pin "1") (pinfunction "1_1") (pintype "passive"))
    )
    (net (code "76") (name "Net-(ISO8-Cathode)") (class "Default")
      (node (ref "ISO8") (pin "2") (pinfunction "Cathode_2") (pintype "passive"))
      (node (ref "RT12") (pin "1") (pinfunction "1_1") (pintype "passive"))
    )
    (net (code "77") (name "Net-(ISO9-Cathode)") (class "Default")
      (node (ref "ISO9") (pin "2") (pinfunction "Cathode_2") (pintype "passive"))
      (node (ref "RT17") (pin "1") (pinfunction "1_1") (pintype "passive"))
    )
    (net (code "78") (name "Net-(ISO10-Cathode)") (class "Default")
      (node (ref "ISO10") (pin "2") (pinfunction "Cathode_2") (pintype "passive"))
      (node (ref "RT19") (pin "1") (pinfunction "1_1") (pintype "passive"))
    )
    (net (code "79") (name "Net-(ISO11-Cathode)") (class "Default")
      (node (ref "ISO11") (pin "2") (pinfunction "Cathode_2") (pintype "passive"))
      (node (ref "RT21") (pin "1") (pinfunction "1_1") (pintype "passive"))
    )
    (net (code "80") (name "Net-(ISO12-Cathode)") (class "Default")
      (node (ref "ISO12") (pin "2") (pinfunction "Cathode_2") (pintype "passive"))
      (node (ref "RT23") (pin "1") (pinfunction "1_1") (pintype "passive"))
    )
    (net (code "81") (name "Net-(ISO13-Cathode)") (class "Default")
      (node (ref "ISO13") (pin "2") (pinfunction "Cathode_2") (pintype "passive"))
      (node (ref "RT24") (pin "1") (pinfunction "1_1") (pintype "passive"))
    )
    (net (code "82") (name "Net-(L1-Pad1)") (class "Default")
      (node (ref "L1") (pin "1") (pintype "passive"))
      (node (ref "R2") (pin "1") (pinfunction "1_1") (pintype "passive"))
    )
    (net (code "83") (name "Net-(U1-BOOT0)") (class "Default")
      (node (ref "R1") (pin "1") (pinfunction "1_1") (pintype "passive"))
      (node (ref "U1") (pin "44") (pinfunction "BOOT0_44") (pintype "passive"))
    )
    (net (code "84") (name "Net-(U1-PD0-0SC)") (class "Default")
      (node (ref "C2") (pin "1") (pinfunction "1_1") (pintype "passive"))
      (node (ref "U1") (pin "5") (pinfunction "PD0-0SC_5") (pintype "passive"))
      (node (ref "Y1") (pin "1") (pinfunction "1_1") (pintype "passive"))
    )
    (net (code "85") (name "Net-(U1-PD1-OSC)") (class "Default")
      (node (ref "C4") (pin "1") (pinfunction "1_1") (pintype "passive"))
      (node (ref "U1") (pin "6") (pinfunction "PD1-OSC_6") (pintype "passive"))
      (node (ref "Y1") (pin "2") (pinfunction "2_2") (pintype "passive"))
    )
    (net (code "86") (name "VCC") (class "Default")
      (node (ref "C1") (pin "1") (pinfunction "1_1") (pintype "passive"))
      (node (ref "C3") (pin "1") (pinfunction "1_1") (pintype "passive"))
      (node (ref "C5") (pin "1") (pinfunction "1_1") (pintype "passive"))
      (node (ref "C6") (pin "1") (pinfunction "1_1") (pintype "passive"))
      (node (ref "C8") (pin "1") (pinfunction "1_1") (pintype "passive"))
      (node (ref "P2") (pin "2") (pinfunction "2_2") (pintype "passive"))
      (node (ref "R2") (pin "2") (pinfunction "2_2") (pintype "passive"))
      (node (ref "U1") (pin "24") (pinfunction "VDD1_24") (pintype "passive"))
      (node (ref "U1") (pin "36") (pinfunction "VDD2_36") (pintype "passive"))
      (node (ref "U1") (pin "48") (pinfunction "VDD3_48") (pintype "passive"))
      (node (ref "U1") (pin "9") (pinfunction "VDDA_9") (pintype "passive"))
      (node (ref "u3") (pin "2") (pinfunction "OUT_2") (pintype "passive"))
    )
    (net (code "87") (name "unconnected-(P2-Pad4)") (class "Default")
      (node (ref "P2") (pin "4") (pinfunction "4_4") (pintype "passive"))
    )
    (net (code "88") (name "unconnected-(P2-Pad7)") (class "Default")
      (node (ref "P2") (pin "7") (pinfunction "7_7") (pintype "passive"))
    )
    (net (code "89") (name "unconnected-(P2-Pad9)") (class "Default")
      (node (ref "P2") (pin "9") (pinfunction "9_9") (pintype "passive"))
    )
    (net (code "90") (name "unconnected-(P2-Pad10)") (class "Default")
      (node (ref "P2") (pin "10") (pinfunction "10_10") (pintype "passive"))
    )
    (net (code "91") (name "unconnected-(P5-Pad1)") (class "Default")
      (node (ref "P5") (pin "1") (pinfunction "1_1") (pintype "passive"))
    )
    (net (code "92") (name "unconnected-(P5-Pad5)") (class "Default")
      (node (ref "P5") (pin "5") (pinfunction "5_5") (pintype "passive"))
    )
    (net (code "93") (name "unconnected-(U1-VBAT-Pad1)") (class "Default")
      (node (ref "U1") (pin "1") (pinfunction "VBAT_1") (pintype "passive"))
    )
    (net (code "94") (name "unconnected-(u2-NOP-Pad4)") (class "Default")
      (node (ref "u2") (pin "4") (pinfunction "NOP_4") (pintype "passive"))
    )
    (net (code "95") (name "unconnected-(u3-NOP-Pad4)") (class "Default")
      (node (ref "u3") (pin "4") (pinfunction "NOP_4") (pintype "passive"))
    )
  )
)
